# SCH_Control-Board_2024-08-24.net
KiCad netlist of a schematic drawn in EasyEDA
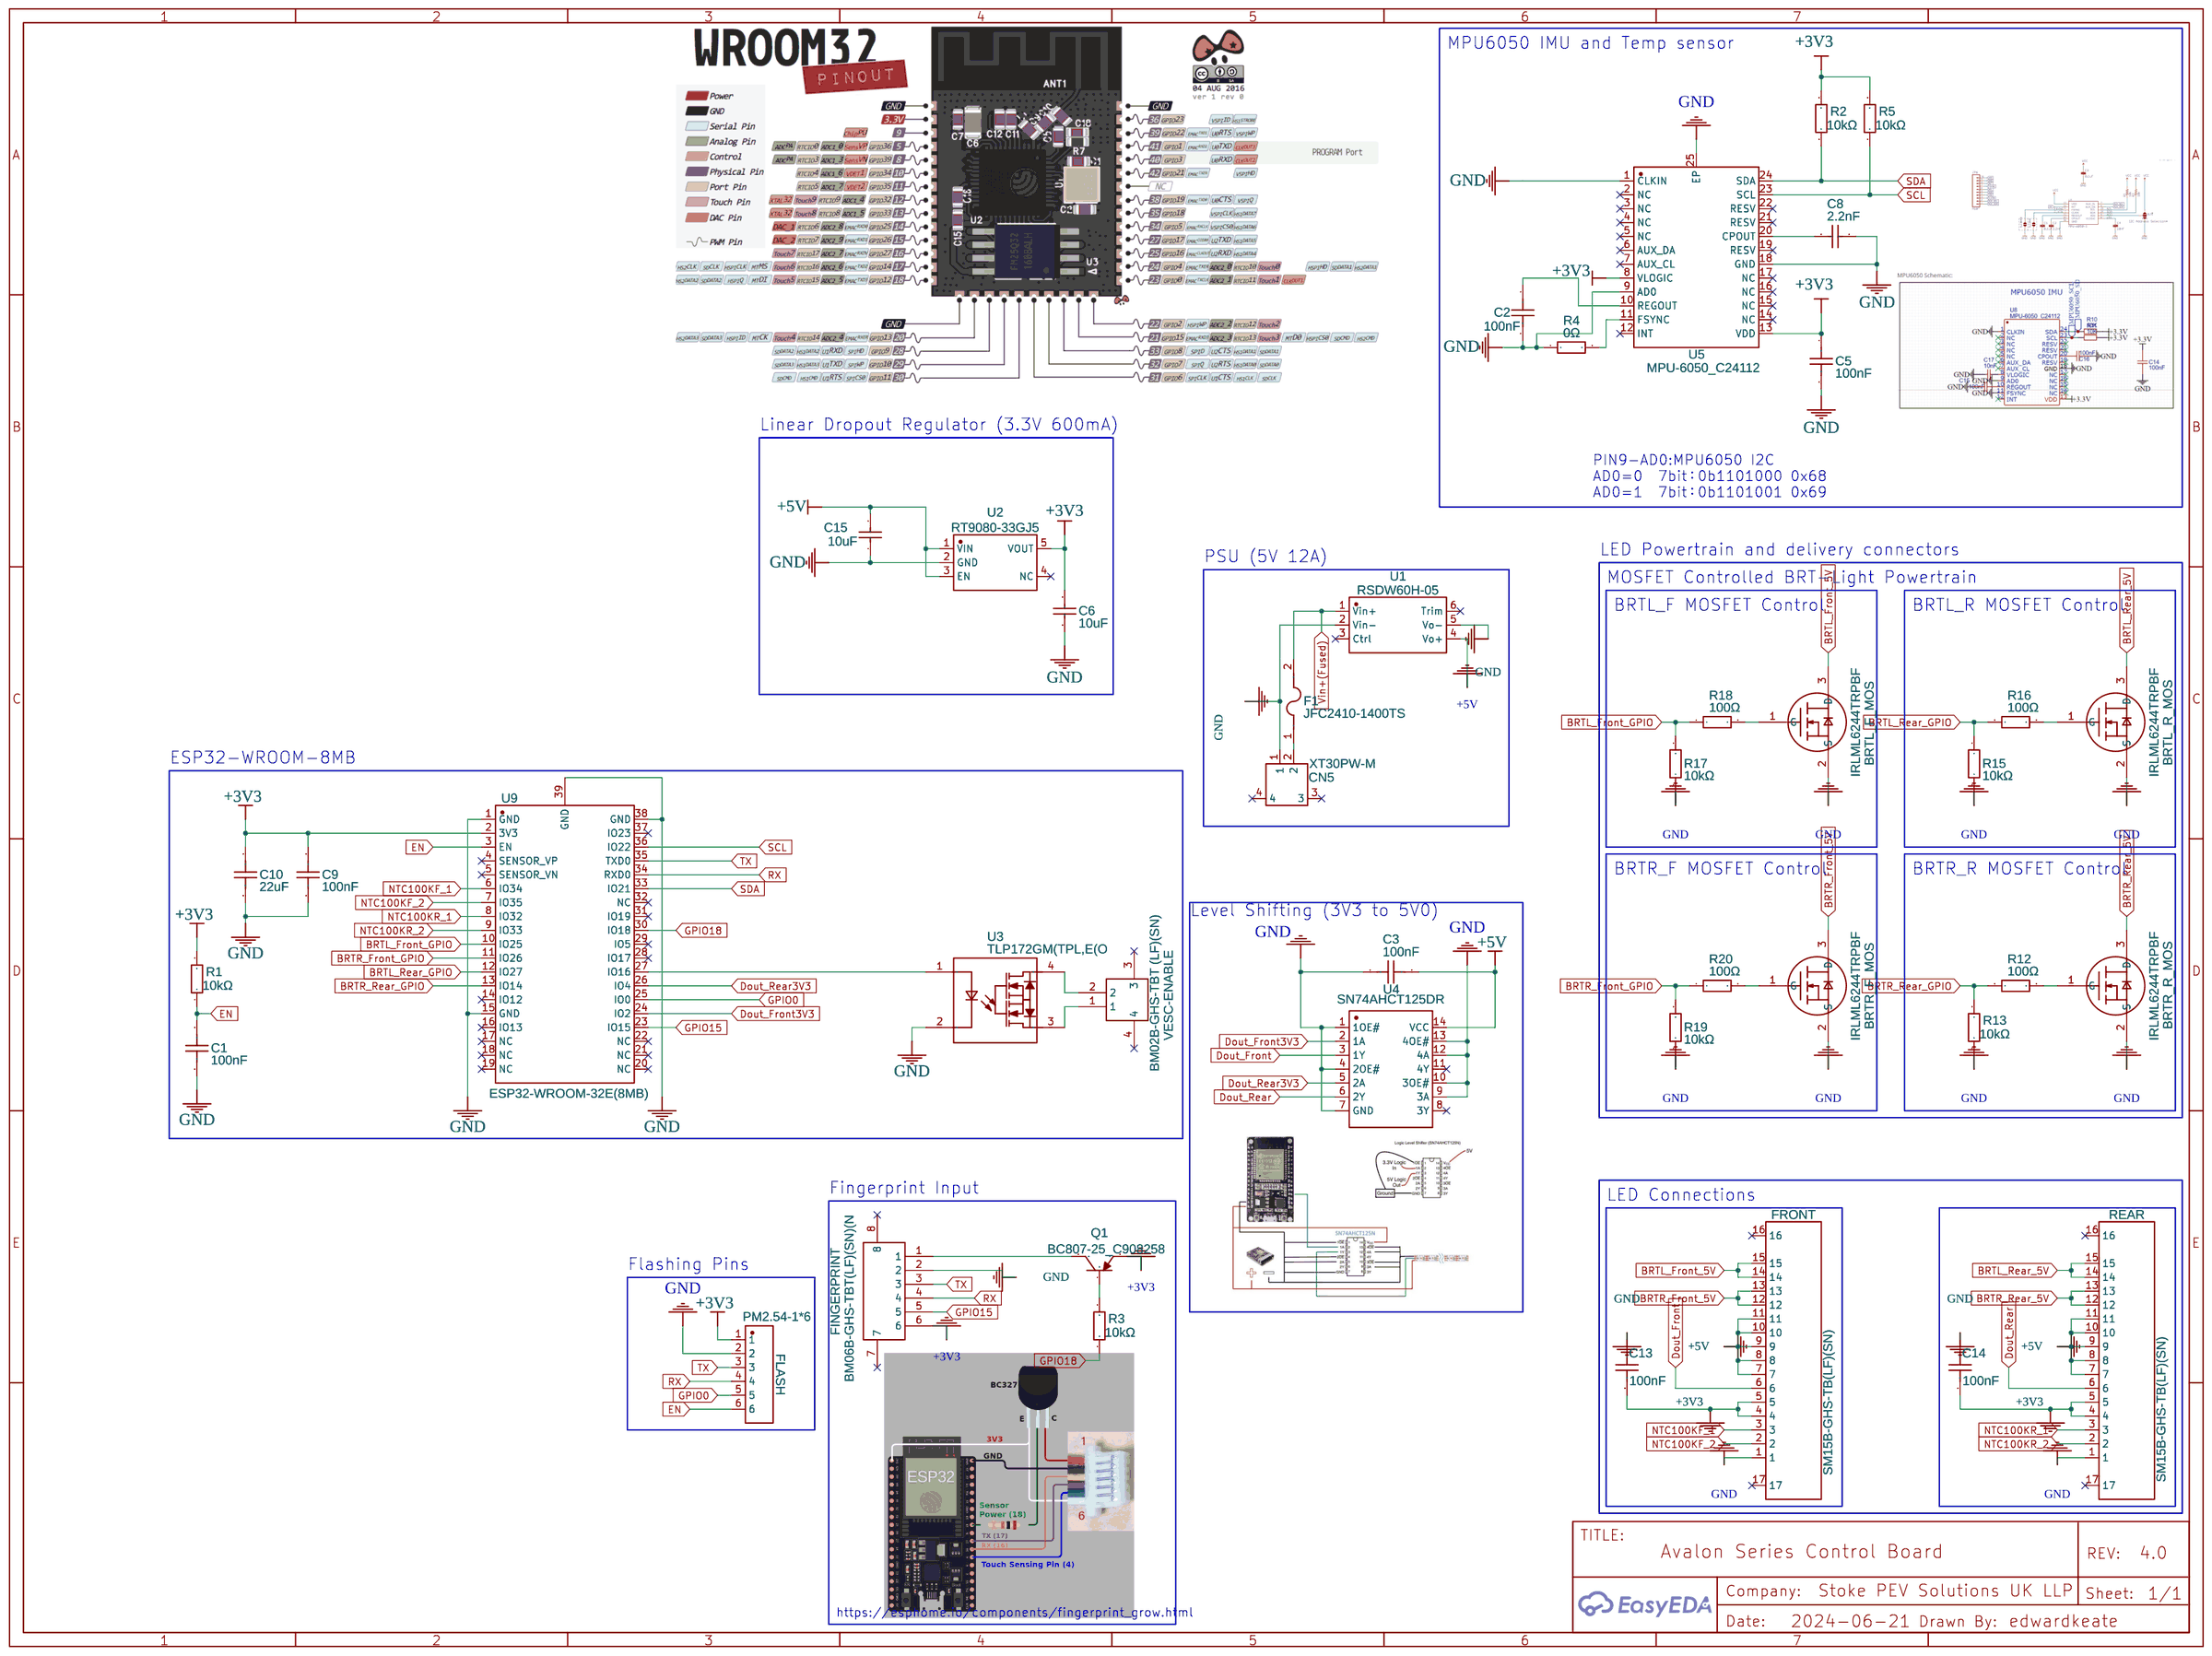
[diagram p0: schematic sheet]

(export (version "E")
  (design (tool "Eeschema 10.0.6"))
  (components
    (comp (ref "BRTL_F_MOS")
      (value "IRLML6244TRPBF")
      (fields (field (name "Manufacturer") "Infineon(英飞凌)"))
      (libsource (lib "") (part "IRLML6244TRPBF"))
    )
    (comp (ref "BRTL_R_MOS")
      (value "IRLML6244TRPBF")
      (fields (field (name "Manufacturer") "Infineon(英飞凌)"))
      (libsource (lib "") (part "IRLML6244TRPBF_1"))
    )
    (comp (ref "BRTR_F_MOS")
      (value "IRLML6244TRPBF")
      (fields (field (name "Manufacturer") "Infineon(英飞凌)"))
      (libsource (lib "") (part "IRLML6244TRPBF_2"))
    )
    (comp (ref "BRTR_R_MOS")
      (value "IRLML6244TRPBF")
      (fields (field (name "Manufacturer") "Infineon(英飞凌)"))
      (libsource (lib "") (part "IRLML6244TRPBF_3"))
    )
    (comp (ref "C1")
      (value "100nF")
      (fields
        (field (name "Manufacturer Part") "CC0603KRX7R9BB104")
        (field (name "Manufacturer") "YAGEO(国巨)")
      )
      (libsource (lib "") (part "CC0603KRX7R9BB104"))
    )
    (comp (ref "C2")
      (value "100nF")
      (fields
        (field (name "Manufacturer Part") "CC0603KRX7R9BB104")
        (field (name "Manufacturer") "YAGEO(国巨)")
      )
      (libsource (lib "") (part "CC0603KRX7R9BB104"))
    )
    (comp (ref "C3")
      (value "100nF")
      (fields
        (field (name "Manufacturer Part") "CC0603KRX7R9BB104")
        (field (name "Manufacturer") "YAGEO(国巨)")
      )
      (libsource (lib "") (part "CC0603KRX7R9BB104_1"))
    )
    (comp (ref "C5")
      (value "100nF")
      (fields
        (field (name "Manufacturer Part") "CC0603KRX7R9BB104")
        (field (name "Manufacturer") "YAGEO(国巨)")
      )
      (libsource (lib "") (part "CC0603KRX7R9BB104"))
    )
    (comp (ref "C6")
      (value "10uF")
      (fields
        (field (name "Manufacturer Part") "CL05A106MQ5NUNC")
        (field (name "Manufacturer") "SAMSUNG(三星)")
      )
      (libsource (lib "") (part "CL05A106MQ5NUNC"))
    )
    (comp (ref "C8")
      (value "2.2nF")
      (fields
        (field (name "Manufacturer Part") "CL21C222JBFNNNE")
        (field (name "Manufacturer") "SAMSUNG(三星)")
      )
      (libsource (lib "") (part "CL21C222JBFNNNE"))
    )
    (comp (ref "C9")
      (value "100nF")
      (fields
        (field (name "Manufacturer Part") "CC0603KRX7R9BB104")
        (field (name "Manufacturer") "YAGEO(国巨)")
      )
      (libsource (lib "") (part "CC0603KRX7R9BB104"))
    )
    (comp (ref "C10")
      (value "22uF")
      (fields
        (field (name "Manufacturer Part") "CL10A226MQ8NRNC")
        (field (name "Manufacturer") "SAMSUNG(三星)")
      )
      (libsource (lib "") (part "CL10A226MQ8NRNC"))
    )
    (comp (ref "C13")
      (value "100nF")
      (fields
        (field (name "Manufacturer Part") "CC0603KRX7R9BB104")
        (field (name "Manufacturer") "YAGEO(国巨)")
      )
      (libsource (lib "") (part "CC0603KRX7R9BB104"))
    )
    (comp (ref "C14")
      (value "100nF")
      (fields
        (field (name "Manufacturer Part") "CC0603KRX7R9BB104")
        (field (name "Manufacturer") "YAGEO(国巨)")
      )
      (libsource (lib "") (part "CC0603KRX7R9BB104"))
    )
    (comp (ref "C15")
      (value "10uF")
      (fields
        (field (name "Manufacturer Part") "CL05A106MQ5NUNC")
        (field (name "Manufacturer") "SAMSUNG(三星)")
      )
      (libsource (lib "") (part "CL05A106MQ5NUNC"))
    )
    (comp (ref "CN5")
      (value "XT30PW-M")
      (fields (field (name "Manufacturer") "AMASS(艾迈斯)"))
      (libsource (lib "") (part "XT30PW-M"))
    )
    (comp (ref "F1")
      (value "JFC2410-1400TS")
      (fields (field (name "Manufacturer") "JDTfuse(集电通)"))
      (libsource (lib "") (part "JFC2410-1400TS"))
    )
    (comp (ref "FINGERPRINT")
      (value "BM06B-GHS-TBT(LF)(SN)(N")
      (fields (field (name "Manufacturer Part") "BM06B-GHS-TBT(LF)(SN)") (field (name "Manufacturer") "JST"))
      (libsource (lib "") (part "BM06B-GHS-TBT(LF)(SN)(N"))
    )
    (comp (ref "FLASH")
      (value "PM2.54-1*6")
      (fields (field (name "Manufacturer") "ZHOURI(洲日)"))
      (libsource (lib "") (part "PM2.54-1*6"))
    )
    (comp (ref "FRONT")
      (value "SM15B-GHS-TB(LF)(SN)")
      (fields (field (name "Manufacturer") "JST"))
      (libsource (lib "") (part "SM15B-GHS-TB(LF)(SN)_1"))
    )
    (comp (ref "Q1")
      (value "BC807-25_C908258")
      (fields (field (name "Manufacturer Part") "BC807-25") (field (name "Manufacturer") "FUXINSEMI(富芯森美)"))
      (libsource (lib "") (part "BC807-25_C908258"))
    )
    (comp (ref "R1")
      (value "10kΩ")
      (fields
        (field (name "Manufacturer Part") "0603WAF1002T5E")
        (field (name "Manufacturer") "UNI-ROYAL(厚声)")
      )
      (libsource (lib "") (part "0603WAF1002T5E"))
    )
    (comp (ref "R2")
      (value "10kΩ")
      (fields
        (field (name "Manufacturer Part") "0603WAF1002T5E")
        (field (name "Manufacturer") "UNI-ROYAL(厚声)")
      )
      (libsource (lib "") (part "0603WAF1002T5E"))
    )
    (comp (ref "R3")
      (value "10kΩ")
      (fields
        (field (name "Manufacturer Part") "0603WAF1002T5E")
        (field (name "Manufacturer") "UNI-ROYAL(厚声)")
      )
      (libsource (lib "") (part "0603WAF1002T5E"))
    )
    (comp (ref "R4")
      (value "0Ω")
      (fields
        (field (name "Manufacturer Part") "0603WAF0000T5E")
        (field (name "Manufacturer") "UNI-ROYAL(厚声)")
      )
      (libsource (lib "") (part "0603WAF0000T5E"))
    )
    (comp (ref "R5")
      (value "10kΩ")
      (fields
        (field (name "Manufacturer Part") "0603WAF1002T5E")
        (field (name "Manufacturer") "UNI-ROYAL(厚声)")
      )
      (libsource (lib "") (part "0603WAF1002T5E"))
    )
    (comp (ref "R12")
      (value "100Ω")
      (fields
        (field (name "Manufacturer Part") "0603WAF1000T5E")
        (field (name "Manufacturer") "UNI-ROYAL(厚声)")
      )
      (libsource (lib "") (part "0603WAF1000T5E"))
    )
    (comp (ref "R13")
      (value "10kΩ")
      (fields
        (field (name "Manufacturer Part") "0603WAF1002T5E")
        (field (name "Manufacturer") "UNI-ROYAL(厚声)")
      )
      (libsource (lib "") (part "0603WAF1002T5E"))
    )
    (comp (ref "R15")
      (value "10kΩ")
      (fields
        (field (name "Manufacturer Part") "0603WAF1002T5E")
        (field (name "Manufacturer") "UNI-ROYAL(厚声)")
      )
      (libsource (lib "") (part "0603WAF1002T5E"))
    )
    (comp (ref "R16")
      (value "100Ω")
      (fields
        (field (name "Manufacturer Part") "0603WAF1000T5E")
        (field (name "Manufacturer") "UNI-ROYAL(厚声)")
      )
      (libsource (lib "") (part "0603WAF1000T5E"))
    )
    (comp (ref "R17")
      (value "10kΩ")
      (fields
        (field (name "Manufacturer Part") "0603WAF1002T5E")
        (field (name "Manufacturer") "UNI-ROYAL(厚声)")
      )
      (libsource (lib "") (part "0603WAF1002T5E"))
    )
    (comp (ref "R18")
      (value "100Ω")
      (fields
        (field (name "Manufacturer Part") "0603WAF1000T5E")
        (field (name "Manufacturer") "UNI-ROYAL(厚声)")
      )
      (libsource (lib "") (part "0603WAF1000T5E"))
    )
    (comp (ref "R19")
      (value "10kΩ")
      (fields
        (field (name "Manufacturer Part") "0603WAF1002T5E")
        (field (name "Manufacturer") "UNI-ROYAL(厚声)")
      )
      (libsource (lib "") (part "0603WAF1002T5E"))
    )
    (comp (ref "R20")
      (value "100Ω")
      (fields
        (field (name "Manufacturer Part") "0603WAF1000T5E")
        (field (name "Manufacturer") "UNI-ROYAL(厚声)")
      )
      (libsource (lib "") (part "0603WAF1000T5E"))
    )
    (comp (ref "REAR")
      (value "SM15B-GHS-TB(LF)(SN)")
      (fields (field (name "Manufacturer") "JST"))
      (libsource (lib "") (part "SM15B-GHS-TB(LF)(SN)"))
    )
    (comp (ref "U1")
      (value "RSDW60H-05")
      (fields (field (name "Manufacturer") "MEAN WELL USA Inc."))
      (libsource (lib "") (part "RSDW60H-05"))
    )
    (comp (ref "U2")
      (value "RT9080-33GJ5")
      (fields (field (name "Manufacturer") "RICHTEK(立锜)"))
      (libsource (lib "") (part "RT9080-33GJ5"))
    )
    (comp (ref "U3")
      (value "TLP172GM(TPL,E(O")
      (fields (field (name "Manufacturer") "TOSHIBA(东芝)"))
      (libsource (lib "") (part "TLP172GM(TPL,E(O"))
    )
    (comp (ref "U4")
      (value "SN74AHCT125DR")
      (fields (field (name "Manufacturer") "TI(德州仪器)"))
      (libsource (lib "") (part "SN74AHCT125DR"))
    )
    (comp (ref "U5")
      (value "MPU-6050_C24112")
      (fields
        (field (name "Manufacturer Part") "MPU-6050")
        (field (name "Manufacturer") "TDK InvenSense(应美盛)")
      )
      (libsource (lib "") (part "MPU-6050_C24112"))
    )
    (comp (ref "U9")
      (value "ESP32-WROOM-32E(8MB)")
      (fields (field (name "Manufacturer") "Espressif Systems"))
      (libsource (lib "") (part "ESP32-WROOM-32E(8MB)"))
    )
    (comp (ref "VESC-ENABLE")
      (value "BM02B-GHS-TBT (LF)(SN)")
      (fields (field (name "Manufacturer Part") "BM02B-GHS-TBT(LF)(SN)") (field (name "Manufacturer") "JST"))
      (libsource (lib "") (part "BM02B-GHS-TBT (LF)(SN)"))
    )
  )
  (nets
    (net (code "1") (name "+3V3") (class "Default")
      (node (ref "C10") (pin "1") (pinfunction "1_1") (pintype "unspecified"))
      (node (ref "C13") (pin "2") (pinfunction "2_2") (pintype "unspecified"))
      (node (ref "C14") (pin "2") (pinfunction "2_2") (pintype "unspecified"))
      (node (ref "C5") (pin "1") (pinfunction "1_1") (pintype "unspecified"))
      (node (ref "C6") (pin "2") (pinfunction "2_2") (pintype "input"))
      (node (ref "C9") (pin "1") (pinfunction "1_1") (pintype "unspecified"))
      (node (ref "FINGERPRINT") (pin "6") (pinfunction "6_6") (pintype "unspecified"))
      (node (ref "FLASH") (pin "1") (pinfunction "1_1") (pintype "unspecified"))
      (node (ref "FRONT") (pin "4") (pinfunction "4_4") (pintype "unspecified"))
      (node (ref "FRONT") (pin "5") (pinfunction "5_5") (pintype "unspecified"))
      (node (ref "Q1") (pin "2") (pinfunction "E_2") (pintype "input"))
      (node (ref "R1") (pin "2") (pinfunction "2_2") (pintype "input"))
      (node (ref "R2") (pin "2") (pinfunction "2_2") (pintype "input"))
      (node (ref "R5") (pin "2") (pinfunction "2_2") (pintype "input"))
      (node (ref "REAR") (pin "4") (pinfunction "4_4") (pintype "unspecified"))
      (node (ref "REAR") (pin "5") (pinfunction "5_5") (pintype "unspecified"))
      (node (ref "U2") (pin "5") (pinfunction "VOUT_5") (pintype "unspecified"))
      (node (ref "U5") (pin "13") (pinfunction "VDD_13") (pintype "unspecified"))
      (node (ref "U5") (pin "8") (pinfunction "VLOGIC_8") (pintype "unspecified"))
      (node (ref "U9") (pin "2") (pinfunction "3V3_2") (pintype "unspecified"))
    )
    (net (code "2") (name "+5V") (class "Default")
      (node (ref "C15") (pin "2") (pinfunction "2_2") (pintype "input"))
      (node (ref "C3") (pin "1") (pinfunction "1_1") (pintype "unspecified"))
      (node (ref "FRONT") (pin "10") (pinfunction "10_10") (pintype "unspecified"))
      (node (ref "FRONT") (pin "11") (pinfunction "11_11") (pintype "unspecified"))
      (node (ref "FRONT") (pin "7") (pinfunction "7_7") (pintype "unspecified"))
      (node (ref "FRONT") (pin "8") (pinfunction "8_8") (pintype "unspecified"))
      (node (ref "FRONT") (pin "9") (pinfunction "9_9") (pintype "unspecified"))
      (node (ref "REAR") (pin "10") (pinfunction "10_10") (pintype "unspecified"))
      (node (ref "REAR") (pin "11") (pinfunction "11_11") (pintype "unspecified"))
      (node (ref "REAR") (pin "7") (pinfunction "7_7") (pintype "unspecified"))
      (node (ref "REAR") (pin "8") (pinfunction "8_8") (pintype "unspecified"))
      (node (ref "REAR") (pin "9") (pinfunction "9_9") (pintype "unspecified"))
      (node (ref "U1") (pin "4") (pinfunction "Vo+_4") (pintype "unspecified"))
      (node (ref "U2") (pin "1") (pinfunction "VIN_1") (pintype "unspecified"))
      (node (ref "U2") (pin "3") (pinfunction "EN_3") (pintype "unspecified"))
      (node (ref "U4") (pin "14") (pinfunction "VCC_14") (pintype "unspecified"))
    )
    (net (code "3") (name "BRTL_Front_5V") (class "Default")
      (node (ref "BRTL_F_MOS") (pin "3") (pinfunction "D_3") (pintype "unspecified"))
      (node (ref "FRONT") (pin "14") (pinfunction "14_14") (pintype "unspecified"))
      (node (ref "FRONT") (pin "15") (pinfunction "15_15") (pintype "unspecified"))
    )
    (net (code "4") (name "BRTL_Front_GPIO") (class "Default")
      (node (ref "R17") (pin "2") (pinfunction "2_2") (pintype "input"))
      (node (ref "R18") (pin "1") (pinfunction "1_1") (pintype "input"))
      (node (ref "U9") (pin "10") (pinfunction "IO25_10") (pintype "unspecified"))
    )
    (net (code "5") (name "BRTL_Rear_5V") (class "Default")
      (node (ref "BRTL_R_MOS") (pin "3") (pinfunction "D_3") (pintype "unspecified"))
      (node (ref "REAR") (pin "14") (pinfunction "14_14") (pintype "unspecified"))
      (node (ref "REAR") (pin "15") (pinfunction "15_15") (pintype "unspecified"))
    )
    (net (code "6") (name "BRTL_Rear_GPIO") (class "Default")
      (node (ref "R15") (pin "2") (pinfunction "2_2") (pintype "input"))
      (node (ref "R16") (pin "1") (pinfunction "1_1") (pintype "input"))
      (node (ref "U9") (pin "12") (pinfunction "IO27_12") (pintype "unspecified"))
    )
    (net (code "7") (name "BRTR_Front_5V") (class "Default")
      (node (ref "BRTR_F_MOS") (pin "3") (pinfunction "D_3") (pintype "unspecified"))
      (node (ref "FRONT") (pin "12") (pinfunction "12_12") (pintype "unspecified"))
      (node (ref "FRONT") (pin "13") (pinfunction "13_13") (pintype "unspecified"))
    )
    (net (code "8") (name "BRTR_Front_GPIO") (class "Default")
      (node (ref "R19") (pin "2") (pinfunction "2_2") (pintype "input"))
      (node (ref "R20") (pin "1") (pinfunction "1_1") (pintype "input"))
      (node (ref "U9") (pin "11") (pinfunction "IO26_11") (pintype "unspecified"))
    )
    (net (code "9") (name "BRTR_Rear_5V") (class "Default")
      (node (ref "BRTR_R_MOS") (pin "3") (pinfunction "D_3") (pintype "unspecified"))
      (node (ref "REAR") (pin "12") (pinfunction "12_12") (pintype "unspecified"))
      (node (ref "REAR") (pin "13") (pinfunction "13_13") (pintype "unspecified"))
    )
    (net (code "10") (name "BRTR_Rear_GPIO") (class "Default")
      (node (ref "R12") (pin "1") (pinfunction "1_1") (pintype "input"))
      (node (ref "R13") (pin "2") (pinfunction "2_2") (pintype "input"))
      (node (ref "U9") (pin "13") (pinfunction "IO14_13") (pintype "unspecified"))
    )
    (net (code "11") (name "Dout_Front") (class "Default")
      (node (ref "FRONT") (pin "6") (pinfunction "6_6") (pintype "unspecified"))
      (node (ref "U4") (pin "3") (pinfunction "1Y_3") (pintype "unspecified"))
    )
    (net (code "12") (name "Dout_Front3V3") (class "Default")
      (node (ref "U4") (pin "2") (pinfunction "1A_2") (pintype "unspecified"))
      (node (ref "U9") (pin "24") (pinfunction "IO2_24") (pintype "unspecified"))
    )
    (net (code "13") (name "Dout_Rear") (class "Default")
      (node (ref "REAR") (pin "6") (pinfunction "6_6") (pintype "unspecified"))
      (node (ref "U4") (pin "6") (pinfunction "2Y_6") (pintype "unspecified"))
    )
    (net (code "14") (name "Dout_Rear3V3") (class "Default")
      (node (ref "U4") (pin "5") (pinfunction "2A_5") (pintype "unspecified"))
      (node (ref "U9") (pin "26") (pinfunction "IO4_26") (pintype "unspecified"))
    )
    (net (code "15") (name "EN") (class "Default")
      (node (ref "C1") (pin "1") (pinfunction "1_1") (pintype "unspecified"))
      (node (ref "FLASH") (pin "6") (pinfunction "6_6") (pintype "unspecified"))
      (node (ref "R1") (pin "1") (pinfunction "1_1") (pintype "input"))
      (node (ref "U9") (pin "3") (pinfunction "EN_3") (pintype "unspecified"))
    )
    (net (code "16") (name "GND") (class "Default")
      (node (ref "BRTL_F_MOS") (pin "2") (pinfunction "S_2") (pintype "unspecified"))
      (node (ref "BRTL_R_MOS") (pin "2") (pinfunction "S_2") (pintype "unspecified"))
      (node (ref "BRTR_F_MOS") (pin "2") (pinfunction "S_2") (pintype "unspecified"))
      (node (ref "BRTR_R_MOS") (pin "2") (pinfunction "S_2") (pintype "unspecified"))
      (node (ref "C1") (pin "2") (pinfunction "2_2") (pintype "unspecified"))
      (node (ref "C10") (pin "2") (pinfunction "2_2") (pintype "unspecified"))
      (node (ref "C13") (pin "1") (pinfunction "1_1") (pintype "unspecified"))
      (node (ref "C14") (pin "1") (pinfunction "1_1") (pintype "unspecified"))
      (node (ref "C15") (pin "1") (pinfunction "1_1") (pintype "input"))
      (node (ref "C2") (pin "2") (pinfunction "2_2") (pintype "unspecified"))
      (node (ref "C3") (pin "2") (pinfunction "2_2") (pintype "unspecified"))
      (node (ref "C5") (pin "2") (pinfunction "2_2") (pintype "unspecified"))
      (node (ref "C6") (pin "1") (pinfunction "1_1") (pintype "input"))
      (node (ref "C8") (pin "2") (pinfunction "2_2") (pintype "input"))
      (node (ref "C9") (pin "2") (pinfunction "2_2") (pintype "unspecified"))
      (node (ref "CN5") (pin "1") (pinfunction "1_1") (pintype "unspecified"))
      (node (ref "FINGERPRINT") (pin "2") (pinfunction "2_2") (pintype "unspecified"))
      (node (ref "FLASH") (pin "2") (pinfunction "2_2") (pintype "unspecified"))
      (node (ref "FRONT") (pin "1") (pinfunction "1_1") (pintype "unspecified"))
      (node (ref "R13") (pin "1") (pinfunction "1_1") (pintype "input"))
      (node (ref "R15") (pin "1") (pinfunction "1_1") (pintype "input"))
      (node (ref "R17") (pin "1") (pinfunction "1_1") (pintype "input"))
      (node (ref "R19") (pin "1") (pinfunction "1_1") (pintype "input"))
      (node (ref "R4") (pin "1") (pinfunction "1_1") (pintype "input"))
      (node (ref "REAR") (pin "1") (pinfunction "1_1") (pintype "unspecified"))
      (node (ref "U1") (pin "2") (pinfunction "Vin-_2") (pintype "unspecified"))
      (node (ref "U1") (pin "5") (pinfunction "Vo-_5") (pintype "unspecified"))
      (node (ref "U2") (pin "2") (pinfunction "GND_2") (pintype "unspecified"))
      (node (ref "U3") (pin "2") (pinfunction "2_2") (pintype "unspecified"))
      (node (ref "U4") (pin "1") (pinfunction "1OE#_1") (pintype "unspecified"))
      (node (ref "U4") (pin "10") (pinfunction "3OE#_10") (pintype "unspecified"))
      (node (ref "U4") (pin "12") (pinfunction "4A_12") (pintype "unspecified"))
      (node (ref "U4") (pin "13") (pinfunction "4OE#_13") (pintype "unspecified"))
      (node (ref "U4") (pin "4") (pinfunction "2OE#_4") (pintype "unspecified"))
      (node (ref "U4") (pin "7") (pinfunction "GND_7") (pintype "unspecified"))
      (node (ref "U4") (pin "9") (pinfunction "3A_9") (pintype "unspecified"))
      (node (ref "U5") (pin "1") (pinfunction "CLKIN_1") (pintype "unspecified"))
      (node (ref "U5") (pin "18") (pinfunction "GND_18") (pintype "unspecified"))
      (node (ref "U5") (pin "25") (pinfunction "EP_25") (pintype "unspecified"))
      (node (ref "U5") (pin "9") (pinfunction "AD0_9") (pintype "unspecified"))
      (node (ref "U9") (pin "1") (pinfunction "GND_1") (pintype "unspecified"))
      (node (ref "U9") (pin "15") (pinfunction "GND_15") (pintype "unspecified"))
      (node (ref "U9") (pin "38") (pinfunction "GND_38") (pintype "unspecified"))
      (node (ref "U9") (pin "39") (pinfunction "GND_39") (pintype "unspecified"))
    )
    (net (code "17") (name "GPIO0") (class "Default")
      (node (ref "FLASH") (pin "5") (pinfunction "5_5") (pintype "unspecified"))
      (node (ref "U9") (pin "25") (pinfunction "IO0_25") (pintype "unspecified"))
    )
    (net (code "18") (name "GPIO15") (class "Default")
      (node (ref "FINGERPRINT") (pin "5") (pinfunction "5_5") (pintype "unspecified"))
      (node (ref "U9") (pin "23") (pinfunction "IO15_23") (pintype "unspecified"))
    )
    (net (code "19") (name "GPIO18") (class "Default")
      (node (ref "R3") (pin "1") (pinfunction "1_1") (pintype "input"))
      (node (ref "U9") (pin "30") (pinfunction "IO18_30") (pintype "unspecified"))
    )
    (net (code "20") (name "NTC100KF_1") (class "Default")
      (node (ref "FRONT") (pin "3") (pinfunction "3_3") (pintype "unspecified"))
      (node (ref "U9") (pin "6") (pinfunction "IO34_6") (pintype "unspecified"))
    )
    (net (code "21") (name "NTC100KF_2") (class "Default")
      (node (ref "FRONT") (pin "2") (pinfunction "2_2") (pintype "unspecified"))
      (node (ref "U9") (pin "7") (pinfunction "IO35_7") (pintype "unspecified"))
    )
    (net (code "22") (name "NTC100KR_1") (class "Default")
      (node (ref "REAR") (pin "3") (pinfunction "3_3") (pintype "unspecified"))
      (node (ref "U9") (pin "8") (pinfunction "IO32_8") (pintype "unspecified"))
    )
    (net (code "23") (name "NTC100KR_2") (class "Default")
      (node (ref "REAR") (pin "2") (pinfunction "2_2") (pintype "unspecified"))
      (node (ref "U9") (pin "9") (pinfunction "IO33_9") (pintype "unspecified"))
    )
    (net (code "24") (name "Net-(BRTL_F_MOS-G)") (class "Default")
      (node (ref "BRTL_F_MOS") (pin "1") (pinfunction "G_1") (pintype "unspecified"))
      (node (ref "R18") (pin "2") (pinfunction "2_2") (pintype "input"))
    )
    (net (code "25") (name "Net-(BRTL_R_MOS-G)") (class "Default")
      (node (ref "BRTL_R_MOS") (pin "1") (pinfunction "G_1") (pintype "unspecified"))
      (node (ref "R16") (pin "2") (pinfunction "2_2") (pintype "input"))
    )
    (net (code "26") (name "Net-(BRTR_F_MOS-G)") (class "Default")
      (node (ref "BRTR_F_MOS") (pin "1") (pinfunction "G_1") (pintype "unspecified"))
      (node (ref "R20") (pin "2") (pinfunction "2_2") (pintype "input"))
    )
    (net (code "27") (name "Net-(BRTR_R_MOS-G)") (class "Default")
      (node (ref "BRTR_R_MOS") (pin "1") (pinfunction "G_1") (pintype "unspecified"))
      (node (ref "R12") (pin "2") (pinfunction "2_2") (pintype "input"))
    )
    (net (code "28") (name "Net-(CN5-Pad2)") (class "Default")
      (node (ref "CN5") (pin "2") (pinfunction "2_2") (pintype "unspecified"))
      (node (ref "F1") (pin "1") (pinfunction "1_1") (pintype "unspecified"))
    )
    (net (code "29") (name "Net-(Q1-B)") (class "Default")
      (node (ref "Q1") (pin "1") (pinfunction "B_1") (pintype "input"))
      (node (ref "R3") (pin "2") (pinfunction "2_2") (pintype "input"))
    )
    (net (code "30") (name "Net-(Q1-C)") (class "Default")
      (node (ref "FINGERPRINT") (pin "1") (pinfunction "1_1") (pintype "unspecified"))
      (node (ref "Q1") (pin "3") (pinfunction "C_3") (pintype "input"))
    )
    (net (code "31") (name "Net-(U3-Pad3)") (class "Default")
      (node (ref "U3") (pin "3") (pinfunction "3_3") (pintype "unspecified"))
      (node (ref "VESC-ENABLE") (pin "1") (pinfunction "1_1") (pintype "unspecified"))
    )
    (net (code "32") (name "Net-(U3-Pad4)") (class "Default")
      (node (ref "U3") (pin "4") (pinfunction "4_4") (pintype "unspecified"))
      (node (ref "VESC-ENABLE") (pin "2") (pinfunction "2_2") (pintype "unspecified"))
    )
    (net (code "33") (name "Net-(U5-CPOUT)") (class "Default")
      (node (ref "C8") (pin "1") (pinfunction "1_1") (pintype "input"))
      (node (ref "U5") (pin "20") (pinfunction "CPOUT_20") (pintype "unspecified"))
    )
    (net (code "34") (name "Net-(U5-FSYNC)") (class "Default")
      (node (ref "R4") (pin "2") (pinfunction "2_2") (pintype "input"))
      (node (ref "U5") (pin "11") (pinfunction "FSYNC_11") (pintype "unspecified"))
    )
    (net (code "35") (name "Net-(U5-REGOUT)") (class "Default")
      (node (ref "C2") (pin "1") (pinfunction "1_1") (pintype "unspecified"))
      (node (ref "U5") (pin "10") (pinfunction "REGOUT_10") (pintype "unspecified"))
    )
    (net (code "36") (name "Net-(U9-IO16)") (class "Default")
      (node (ref "U3") (pin "1") (pinfunction "1_1") (pintype "unspecified"))
      (node (ref "U9") (pin "27") (pinfunction "IO16_27") (pintype "unspecified"))
    )
    (net (code "37") (name "RX") (class "Default")
      (node (ref "FINGERPRINT") (pin "4") (pinfunction "4_4") (pintype "unspecified"))
      (node (ref "FLASH") (pin "4") (pinfunction "4_4") (pintype "unspecified"))
      (node (ref "U9") (pin "34") (pinfunction "RXD0_34") (pintype "unspecified"))
    )
    (net (code "38") (name "SCL") (class "Default")
      (node (ref "R5") (pin "1") (pinfunction "1_1") (pintype "input"))
      (node (ref "U5") (pin "23") (pinfunction "SCL_23") (pintype "unspecified"))
      (node (ref "U9") (pin "36") (pinfunction "IO22_36") (pintype "unspecified"))
    )
    (net (code "39") (name "SDA") (class "Default")
      (node (ref "R2") (pin "1") (pinfunction "1_1") (pintype "input"))
      (node (ref "U5") (pin "24") (pinfunction "SDA_24") (pintype "unspecified"))
      (node (ref "U9") (pin "33") (pinfunction "IO21_33") (pintype "unspecified"))
    )
    (net (code "40") (name "TX") (class "Default")
      (node (ref "FINGERPRINT") (pin "3") (pinfunction "3_3") (pintype "unspecified"))
      (node (ref "FLASH") (pin "3") (pinfunction "3_3") (pintype "unspecified"))
      (node (ref "U9") (pin "35") (pinfunction "TXD0_35") (pintype "unspecified"))
    )
    (net (code "41") (name "Vin+(Fused)") (class "Default")
      (node (ref "F1") (pin "2") (pinfunction "2_2") (pintype "unspecified"))
      (node (ref "U1") (pin "1") (pinfunction "Vin+_1") (pintype "unspecified"))
    )
    (net (code "42") (name "unconnected-(CN5-Pad3)") (class "Default")
      (node (ref "CN5") (pin "3") (pinfunction "3_3") (pintype "unspecified+no_connect"))
    )
    (net (code "43") (name "unconnected-(CN5-Pad4)") (class "Default")
      (node (ref "CN5") (pin "4") (pinfunction "4_4") (pintype "unspecified+no_connect"))
    )
    (net (code "44") (name "unconnected-(FINGERPRINT-Pad7)") (class "Default")
      (node (ref "FINGERPRINT") (pin "7") (pinfunction "7_7") (pintype "unspecified+no_connect"))
    )
    (net (code "45") (name "unconnected-(FINGERPRINT-Pad8)") (class "Default")
      (node (ref "FINGERPRINT") (pin "8") (pinfunction "8_8") (pintype "unspecified+no_connect"))
    )
    (net (code "46") (name "unconnected-(FRONT-Pad16)") (class "Default")
      (node (ref "FRONT") (pin "16") (pinfunction "16_16") (pintype "unspecified+no_connect"))
    )
    (net (code "47") (name "unconnected-(FRONT-Pad17)") (class "Default")
      (node (ref "FRONT") (pin "17") (pinfunction "17_17") (pintype "unspecified+no_connect"))
    )
    (net (code "48") (name "unconnected-(REAR-Pad16)") (class "Default")
      (node (ref "REAR") (pin "16") (pinfunction "16_16") (pintype "unspecified+no_connect"))
    )
    (net (code "49") (name "unconnected-(REAR-Pad17)") (class "Default")
      (node (ref "REAR") (pin "17") (pinfunction "17_17") (pintype "unspecified+no_connect"))
    )
    (net (code "50") (name "unconnected-(U1-Ctrl-Pad3)") (class "Default")
      (node (ref "U1") (pin "3") (pinfunction "Ctrl_3") (pintype "unspecified+no_connect"))
    )
    (net (code "51") (name "unconnected-(U1-Trim-Pad6)") (class "Default")
      (node (ref "U1") (pin "6") (pinfunction "Trim_6") (pintype "unspecified+no_connect"))
    )
    (net (code "52") (name "unconnected-(U2-NC-Pad4)") (class "Default")
      (node (ref "U2") (pin "4") (pinfunction "NC_4") (pintype "unspecified+no_connect"))
    )
    (net (code "53") (name "unconnected-(U4-3Y-Pad8)") (class "Default")
      (node (ref "U4") (pin "8") (pinfunction "3Y_8") (pintype "unspecified+no_connect"))
    )
    (net (code "54") (name "unconnected-(U4-4Y-Pad11)") (class "Default")
      (node (ref "U4") (pin "11") (pinfunction "4Y_11") (pintype "unspecified+no_connect"))
    )
    (net (code "55") (name "unconnected-(U5-AUX_CL-Pad7)") (class "Default")
      (node (ref "U5") (pin "7") (pinfunction "AUX_CL_7") (pintype "unspecified+no_connect"))
    )
    (net (code "56") (name "unconnected-(U5-AUX_DA-Pad6)") (class "Default")
      (node (ref "U5") (pin "6") (pinfunction "AUX_DA_6") (pintype "unspecified+no_connect"))
    )
    (net (code "57") (name "unconnected-(U5-INT-Pad12)") (class "Default")
      (node (ref "U5") (pin "12") (pinfunction "INT_12") (pintype "unspecified+no_connect"))
    )
    (net (code "58") (name "unconnected-(U5-NC-Pad2)") (class "Default")
      (node (ref "U5") (pin "2") (pinfunction "NC_2") (pintype "unspecified+no_connect"))
    )
    (net (code "59") (name "unconnected-(U5-NC-Pad3)") (class "Default")
      (node (ref "U5") (pin "3") (pinfunction "NC_3") (pintype "unspecified+no_connect"))
    )
    (net (code "60") (name "unconnected-(U5-NC-Pad4)") (class "Default")
      (node (ref "U5") (pin "4") (pinfunction "NC_4") (pintype "unspecified+no_connect"))
    )
    (net (code "61") (name "unconnected-(U5-NC-Pad5)") (class "Default")
      (node (ref "U5") (pin "5") (pinfunction "NC_5") (pintype "unspecified+no_connect"))
    )
    (net (code "62") (name "unconnected-(U5-NC-Pad14)") (class "Default")
      (node (ref "U5") (pin "14") (pinfunction "NC_14") (pintype "unspecified+no_connect"))
    )
    (net (code "63") (name "unconnected-(U5-NC-Pad15)") (class "Default")
      (node (ref "U5") (pin "15") (pinfunction "NC_15") (pintype "unspecified+no_connect"))
    )
    (net (code "64") (name "unconnected-(U5-NC-Pad16)") (class "Default")
      (node (ref "U5") (pin "16") (pinfunction "NC_16") (pintype "unspecified+no_connect"))
    )
    (net (code "65") (name "unconnected-(U5-NC-Pad17)") (class "Default")
      (node (ref "U5") (pin "17") (pinfunction "NC_17") (pintype "unspecified+no_connect"))
    )
    (net (code "66") (name "unconnected-(U5-RESV-Pad19)") (class "Default")
      (node (ref "U5") (pin "19") (pinfunction "RESV_19") (pintype "unspecified+no_connect"))
    )
    (net (code "67") (name "unconnected-(U5-RESV-Pad21)") (class "Default")
      (node (ref "U5") (pin "21") (pinfunction "RESV_21") (pintype "unspecified+no_connect"))
    )
    (net (code "68") (name "unconnected-(U5-RESV-Pad22)") (class "Default")
      (node (ref "U5") (pin "22") (pinfunction "RESV_22") (pintype "unspecified+no_connect"))
    )
    (net (code "69") (name "unconnected-(U9-IO5-Pad29)") (class "Default")
      (node (ref "U9") (pin "29") (pinfunction "IO5_29") (pintype "unspecified+no_connect"))
    )
    (net (code "70") (name "unconnected-(U9-IO12-Pad14)") (class "Default")
      (node (ref "U9") (pin "14") (pinfunction "IO12_14") (pintype "unspecified+no_connect"))
    )
    (net (code "71") (name "unconnected-(U9-IO13-Pad16)") (class "Default")
      (node (ref "U9") (pin "16") (pinfunction "IO13_16") (pintype "unspecified+no_connect"))
    )
    (net (code "72") (name "unconnected-(U9-IO17-Pad28)") (class "Default")
      (node (ref "U9") (pin "28") (pinfunction "IO17_28") (pintype "unspecified+no_connect"))
    )
    (net (code "73") (name "unconnected-(U9-IO19-Pad31)") (class "Default")
      (node (ref "U9") (pin "31") (pinfunction "IO19_31") (pintype "unspecified+no_connect"))
    )
    (net (code "74") (name "unconnected-(U9-IO23-Pad37)") (class "Default")
      (node (ref "U9") (pin "37") (pinfunction "IO23_37") (pintype "unspecified+no_connect"))
    )
    (net (code "75") (name "unconnected-(U9-NC-Pad17)") (class "Default")
      (node (ref "U9") (pin "17") (pinfunction "NC_17") (pintype "unspecified+no_connect"))
    )
    (net (code "76") (name "unconnected-(U9-NC-Pad18)") (class "Default")
      (node (ref "U9") (pin "18") (pinfunction "NC_18") (pintype "unspecified+no_connect"))
    )
    (net (code "77") (name "unconnected-(U9-NC-Pad19)") (class "Default")
      (node (ref "U9") (pin "19") (pinfunction "NC_19") (pintype "unspecified+no_connect"))
    )
    (net (code "78") (name "unconnected-(U9-NC-Pad20)") (class "Default")
      (node (ref "U9") (pin "20") (pinfunction "NC_20") (pintype "unspecified+no_connect"))
    )
    (net (code "79") (name "unconnected-(U9-NC-Pad21)") (class "Default")
      (node (ref "U9") (pin "21") (pinfunction "NC_21") (pintype "unspecified+no_connect"))
    )
    (net (code "80") (name "unconnected-(U9-NC-Pad22)") (class "Default")
      (node (ref "U9") (pin "22") (pinfunction "NC_22") (pintype "unspecified+no_connect"))
    )
    (net (code "81") (name "unconnected-(U9-NC-Pad32)") (class "Default")
      (node (ref "U9") (pin "32") (pinfunction "NC_32") (pintype "unspecified+no_connect"))
    )
    (net (code "82") (name "unconnected-(U9-SENSOR_VN-Pad5)") (class "Default")
      (node (ref "U9") (pin "5") (pinfunction "SENSOR_VN_5") (pintype "unspecified+no_connect"))
    )
    (net (code "83") (name "unconnected-(U9-SENSOR_VP-Pad4)") (class "Default")
      (node (ref "U9") (pin "4") (pinfunction "SENSOR_VP_4") (pintype "unspecified+no_connect"))
    )
    (net (code "84") (name "unconnected-(VESC-ENABLE-Pad3)") (class "Default")
      (node (ref "VESC-ENABLE") (pin "3") (pinfunction "3_3") (pintype "unspecified+no_connect"))
    )
    (net (code "85") (name "unconnected-(VESC-ENABLE-Pad4)") (class "Default")
      (node (ref "VESC-ENABLE") (pin "4") (pinfunction "4_4") (pintype "unspecified+no_connect"))
    )
  )
)
